# buck_converter.net
KiCad netlist of a schematic drawn in Altium Designer
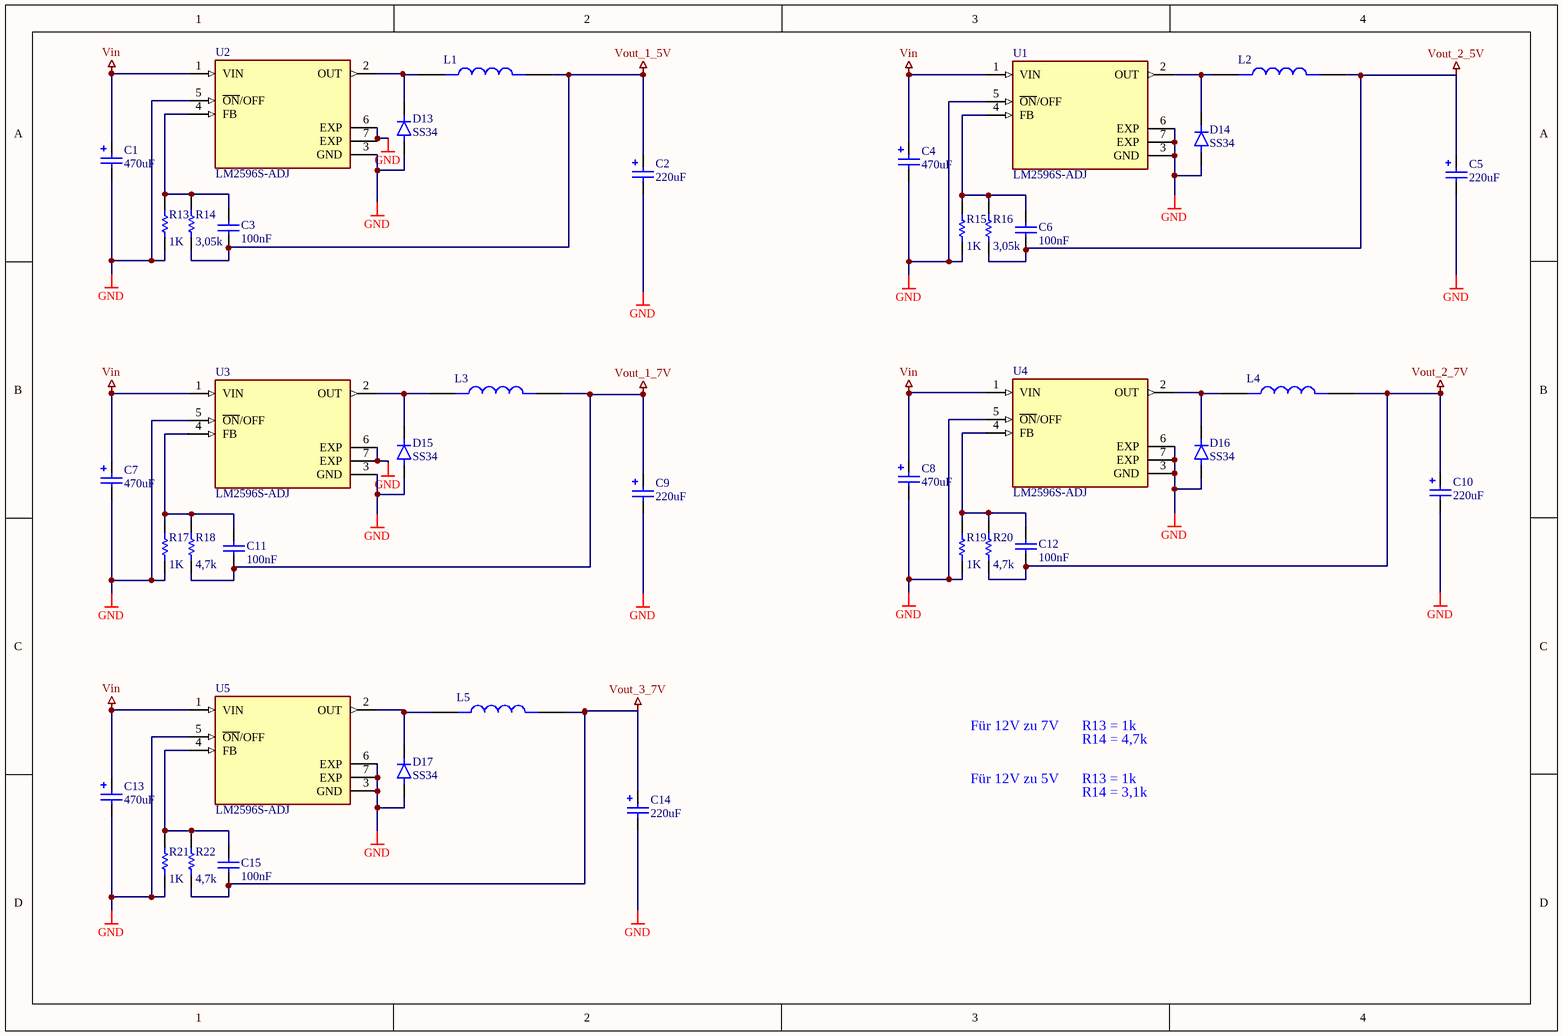
[diagram p0: buck_converter.SchDoc]

(export (version "E")
  (design (tool "Eeschema 10.0.6"))
  (components
    (comp (ref "C1")
      (value "470uF")
      (footprint "CAP_EEEFK1H471AM")
      (description "Elko")
      (fields (field (name "Comment") "Cap"))
      (libsource (lib "HTL-sym-2021_04") (part "ELKO"))
    )
    (comp (ref "C2")
      (value "220uF")
      (footprint "CAPAE1030X1080N_UWT1H221MNL1GS")
      (description "Elko")
      (fields (field (name "Comment") "Cap"))
      (libsource (lib "HTL-sym-2021_04") (part "ELKO"))
    )
    (comp (ref "C3")
      (value "100nF")
      (footprint "RES_ERJB3CFR15V")
      (description "Kondensator")
      (fields (field (name "Comment") "Cap"))
      (libsource (lib "HTL-sym-2021_04") (part "KO"))
    )
    (comp (ref "C4")
      (value "470uF")
      (footprint "CAP_EEEFK1H471AM")
      (description "Elko")
      (fields (field (name "Comment") "Cap"))
      (libsource (lib "HTL-sym-2021_04") (part "ELKO"))
    )
    (comp (ref "C5")
      (value "220uF")
      (footprint "CAPAE1030X1080N_UWT1H221MNL1GS")
      (description "Elko")
      (fields (field (name "Comment") "Cap"))
      (libsource (lib "HTL-sym-2021_04") (part "ELKO"))
    )
    (comp (ref "C6")
      (value "100nF")
      (footprint "RES_ERJB3CFR15V")
      (description "Kondensator")
      (fields (field (name "Comment") "Cap"))
      (libsource (lib "HTL-sym-2021_04") (part "KO"))
    )
    (comp (ref "C7")
      (value "470uF")
      (footprint "CAP_EEEFK1H471AM")
      (description "Elko")
      (fields (field (name "Comment") "Cap"))
      (libsource (lib "HTL-sym-2021_04") (part "ELKO"))
    )
    (comp (ref "C8")
      (value "470uF")
      (footprint "CAP_EEEFK1H471AM")
      (description "Elko")
      (fields (field (name "Comment") "Cap"))
      (libsource (lib "HTL-sym-2021_04") (part "ELKO"))
    )
    (comp (ref "C9")
      (value "220uF")
      (footprint "CAPAE1030X1080N_UWT1H221MNL1GS")
      (description "Elko")
      (fields (field (name "Comment") "Cap"))
      (libsource (lib "HTL-sym-2021_04") (part "ELKO"))
    )
    (comp (ref "C10")
      (value "220uF")
      (footprint "CAPAE1030X1080N_UWT1H221MNL1GS")
      (description "Elko")
      (fields (field (name "Comment") "Cap"))
      (libsource (lib "HTL-sym-2021_04") (part "ELKO"))
    )
    (comp (ref "C11")
      (value "100nF")
      (footprint "RES_ERJB3CFR15V")
      (description "Kondensator")
      (fields (field (name "Comment") "Cap"))
      (libsource (lib "HTL-sym-2021_04") (part "KO"))
    )
    (comp (ref "C12")
      (value "100nF")
      (footprint "RES_ERJB3CFR15V")
      (description "Kondensator")
      (fields (field (name "Comment") "Cap"))
      (libsource (lib "HTL-sym-2021_04") (part "KO"))
    )
    (comp (ref "C13")
      (value "470uF")
      (footprint "CAP_EEEFK1H471AM")
      (description "Elko")
      (fields (field (name "Comment") "Cap"))
      (libsource (lib "HTL-sym-2021_04") (part "ELKO"))
    )
    (comp (ref "C14")
      (value "220uF")
      (footprint "CAPAE1030X1080N_UWT1H221MNL1GS")
      (description "Elko")
      (fields (field (name "Comment") "Cap"))
      (libsource (lib "HTL-sym-2021_04") (part "ELKO"))
    )
    (comp (ref "C15")
      (value "100nF")
      (footprint "RES_ERJB3CFR15V")
      (description "Kondensator")
      (fields (field (name "Comment") "Cap"))
      (libsource (lib "HTL-sym-2021_04") (part "KO"))
    )
    (comp (ref "D13")
      (value "SS34")
      (footprint "DIOMELF3414N")
      (description "Diode Standard 100 V 200mA Surface Mount SOD-80")
      (fields (field (name "MF") "ON Semiconductor") (field (name "MP") "FDLL4148"))
      (libsource (lib "FDLL4148") (part "FDLL4148"))
    )
    (comp (ref "D14")
      (value "SS34")
      (footprint "DIOMELF3414N")
      (description "Diode Standard 100 V 200mA Surface Mount SOD-80")
      (fields (field (name "MF") "ON Semiconductor") (field (name "MP") "FDLL4148"))
      (libsource (lib "FDLL4148") (part "FDLL4148"))
    )
    (comp (ref "D15")
      (value "SS34")
      (footprint "DIOMELF3414N")
      (description "Diode Standard 100 V 200mA Surface Mount SOD-80")
      (fields (field (name "MF") "ON Semiconductor") (field (name "MP") "FDLL4148"))
      (libsource (lib "FDLL4148") (part "FDLL4148"))
    )
    (comp (ref "D16")
      (value "SS34")
      (footprint "DIOMELF3414N")
      (description "Diode Standard 100 V 200mA Surface Mount SOD-80")
      (fields (field (name "MF") "ON Semiconductor") (field (name "MP") "FDLL4148"))
      (libsource (lib "FDLL4148") (part "FDLL4148"))
    )
    (comp (ref "D17")
      (value "SS34")
      (footprint "DIOMELF3414N")
      (description "Diode Standard 100 V 200mA Surface Mount SOD-80")
      (fields (field (name "MF") "ON Semiconductor") (field (name "MP") "FDLL4148"))
      (libsource (lib "FDLL4148") (part "FDLL4148"))
    )
    (comp (ref "L1")
      (value "MLF2012C680KT000")
      (footprint "IND_SRN6045TA-680M")
      (description "68ÂµH Shielded Multilayer Inductor 2mA 2.9Ohm Max 0805 (2012 Metric)")
      (fields (field (name "MF") "{'manufacturer': u'TDK Corporation'}"))
      (libsource (lib "MLF2012C680KT000") (part "MLF2012C680KT000"))
    )
    (comp (ref "L2")
      (value "MLF2012C680KT000")
      (footprint "IND_SRN6045TA-680M")
      (description "68ÂµH Shielded Multilayer Inductor 2mA 2.9Ohm Max 0805 (2012 Metric)")
      (fields (field (name "MF") "{'manufacturer': u'TDK Corporation'}"))
      (libsource (lib "MLF2012C680KT000") (part "MLF2012C680KT000"))
    )
    (comp (ref "L3")
      (value "MLF2012C680KT000")
      (footprint "IND_SRN6045TA-680M")
      (description "68ÂµH Shielded Multilayer Inductor 2mA 2.9Ohm Max 0805 (2012 Metric)")
      (fields (field (name "MF") "{'manufacturer': u'TDK Corporation'}"))
      (libsource (lib "MLF2012C680KT000") (part "MLF2012C680KT000"))
    )
    (comp (ref "L4")
      (value "MLF2012C680KT000")
      (footprint "IND_SRN6045TA-680M")
      (description "68ÂµH Shielded Multilayer Inductor 2mA 2.9Ohm Max 0805 (2012 Metric)")
      (fields (field (name "MF") "{'manufacturer': u'TDK Corporation'}"))
      (libsource (lib "MLF2012C680KT000") (part "MLF2012C680KT000"))
    )
    (comp (ref "L5")
      (value "MLF2012C680KT000")
      (footprint "IND_SRN6045TA-680M")
      (description "68ÂµH Shielded Multilayer Inductor 2mA 2.9Ohm Max 0805 (2012 Metric)")
      (fields (field (name "MF") "{'manufacturer': u'TDK Corporation'}"))
      (libsource (lib "MLF2012C680KT000") (part "MLF2012C680KT000"))
    )
    (comp (ref "R13")
      (value "1K")
      (footprint "RES_ERJB3CFR15V")
      (description "Resistor")
      (fields (field (name "Comment") "Res1") (field (name "PUBLISHER") "Altium Limited"))
      (libsource (lib "Miscellaneous Devices") (part "Res1"))
    )
    (comp (ref "R14")
      (value "3,05k")
      (footprint "RES_ERJB3CFR15V")
      (description "Resistor")
      (fields (field (name "Comment") "Res1") (field (name "PUBLISHER") "Altium Limited"))
      (libsource (lib "Miscellaneous Devices") (part "Res1"))
    )
    (comp (ref "R15")
      (value "1K")
      (footprint "RES_ERJB3CFR15V")
      (description "Resistor")
      (fields (field (name "Comment") "Res1") (field (name "PUBLISHER") "Altium Limited"))
      (libsource (lib "Miscellaneous Devices") (part "Res1"))
    )
    (comp (ref "R16")
      (value "3,05k")
      (footprint "RES_ERJB3CFR15V")
      (description "Resistor")
      (fields (field (name "Comment") "Res1") (field (name "PUBLISHER") "Altium Limited"))
      (libsource (lib "Miscellaneous Devices") (part "Res1"))
    )
    (comp (ref "R17")
      (value "1K")
      (footprint "RES_ERJB3CFR15V")
      (description "Resistor")
      (fields (field (name "Comment") "Res1") (field (name "PUBLISHER") "Altium Limited"))
      (libsource (lib "Miscellaneous Devices") (part "Res1"))
    )
    (comp (ref "R18")
      (value "4,7k")
      (footprint "RES_ERJB3CFR15V")
      (description "Resistor")
      (fields (field (name "Comment") "Res1") (field (name "PUBLISHER") "Altium Limited"))
      (libsource (lib "Miscellaneous Devices") (part "Res1"))
    )
    (comp (ref "R19")
      (value "1K")
      (footprint "RES_ERJB3CFR15V")
      (description "Resistor")
      (fields (field (name "Comment") "Res1") (field (name "PUBLISHER") "Altium Limited"))
      (libsource (lib "Miscellaneous Devices") (part "Res1"))
    )
    (comp (ref "R20")
      (value "4,7k")
      (footprint "RES_ERJB3CFR15V")
      (description "Resistor")
      (fields (field (name "Comment") "Res1") (field (name "PUBLISHER") "Altium Limited"))
      (libsource (lib "Miscellaneous Devices") (part "Res1"))
    )
    (comp (ref "R21")
      (value "1K")
      (footprint "RES_ERJB3CFR15V")
      (description "Resistor")
      (fields (field (name "Comment") "Res1") (field (name "PUBLISHER") "Altium Limited"))
      (libsource (lib "Miscellaneous Devices") (part "Res1"))
    )
    (comp (ref "R22")
      (value "4,7k")
      (footprint "RES_ERJB3CFR15V")
      (description "Resistor")
      (fields (field (name "Comment") "Res1") (field (name "PUBLISHER") "Altium Limited"))
      (libsource (lib "Miscellaneous Devices") (part "Res1"))
    )
    (comp (ref "U1")
      (value "LM2596S-ADJ")
      (footprint "VREG_LM2596SX-5.0_NOPB")
      (description "SIMPLE SWITCHERÂ® 4.5V to 40V, 3A Low Component Count Step-Down Regulator 5-DDPAK/TO-263")
      (fields (field (name "MF") "Texas Instruments") (field (name "MP") "LM2596S-3.3"))
      (libsource (lib "LM2596S-3.3") (part "LM2596S-3.3"))
    )
    (comp (ref "U2")
      (value "LM2596S-ADJ")
      (footprint "VREG_LM2596SX-5.0_NOPB")
      (description "SIMPLE SWITCHERÂ® 4.5V to 40V, 3A Low Component Count Step-Down Regulator 5-DDPAK/TO-263")
      (fields (field (name "MF") "Texas Instruments") (field (name "MP") "LM2596S-3.3"))
      (libsource (lib "LM2596S-3.3") (part "LM2596S-3.3"))
    )
    (comp (ref "U3")
      (value "LM2596S-ADJ")
      (footprint "VREG_LM2596SX-5.0_NOPB")
      (description "SIMPLE SWITCHERÂ® 4.5V to 40V, 3A Low Component Count Step-Down Regulator 5-DDPAK/TO-263")
      (fields (field (name "MF") "Texas Instruments") (field (name "MP") "LM2596S-3.3"))
      (libsource (lib "LM2596S-3.3") (part "LM2596S-3.3"))
    )
    (comp (ref "U4")
      (value "LM2596S-ADJ")
      (footprint "VREG_LM2596SX-5.0_NOPB")
      (description "SIMPLE SWITCHERÂ® 4.5V to 40V, 3A Low Component Count Step-Down Regulator 5-DDPAK/TO-263")
      (fields (field (name "MF") "Texas Instruments") (field (name "MP") "LM2596S-3.3"))
      (libsource (lib "LM2596S-3.3") (part "LM2596S-3.3"))
    )
    (comp (ref "U5")
      (value "LM2596S-ADJ")
      (footprint "VREG_LM2596SX-5.0_NOPB")
      (description "SIMPLE SWITCHERÂ® 4.5V to 40V, 3A Low Component Count Step-Down Regulator 5-DDPAK/TO-263")
      (fields (field (name "MF") "Texas Instruments") (field (name "MP") "LM2596S-3.3"))
      (libsource (lib "LM2596S-3.3") (part "LM2596S-3.3"))
    )
  )
  (nets
    (net (code "1") (name "GND") (class "Default")
      (node (ref "C1") (pin "2") (pinfunction "2_2") (pintype "passive"))
      (node (ref "C10") (pin "2") (pinfunction "2_2") (pintype "passive"))
      (node (ref "C13") (pin "2") (pinfunction "2_2") (pintype "passive"))
      (node (ref "C14") (pin "2") (pinfunction "2_2") (pintype "passive"))
      (node (ref "C2") (pin "2") (pinfunction "2_2") (pintype "passive"))
      (node (ref "C4") (pin "2") (pinfunction "2_2") (pintype "passive"))
      (node (ref "C5") (pin "2") (pinfunction "2_2") (pintype "passive"))
      (node (ref "C7") (pin "2") (pinfunction "2_2") (pintype "passive"))
      (node (ref "C8") (pin "2") (pinfunction "2_2") (pintype "passive"))
      (node (ref "C9") (pin "2") (pinfunction "2_2") (pintype "passive"))
      (node (ref "D13") (pin "A") (pinfunction "A_A") (pintype "passive"))
      (node (ref "D14") (pin "A") (pinfunction "A_A") (pintype "passive"))
      (node (ref "D15") (pin "A") (pinfunction "A_A") (pintype "passive"))
      (node (ref "D16") (pin "A") (pinfunction "A_A") (pintype "passive"))
      (node (ref "D17") (pin "A") (pinfunction "A_A") (pintype "passive"))
      (node (ref "R13") (pin "1") (pinfunction "1_1") (pintype "passive"))
      (node (ref "R15") (pin "1") (pinfunction "1_1") (pintype "passive"))
      (node (ref "R17") (pin "1") (pinfunction "1_1") (pintype "passive"))
      (node (ref "R19") (pin "1") (pinfunction "1_1") (pintype "passive"))
      (node (ref "R21") (pin "1") (pinfunction "1_1") (pintype "passive"))
      (node (ref "U1") (pin "3") (pinfunction "GND_3") (pintype "power_in"))
      (node (ref "U1") (pin "5") (pinfunction "~{ON}/OFF_5") (pintype "input"))
      (node (ref "U1") (pin "6") (pinfunction "EXP_6") (pintype "power_in"))
      (node (ref "U1") (pin "7") (pinfunction "EXP_7") (pintype "power_in"))
      (node (ref "U2") (pin "3") (pinfunction "GND_3") (pintype "power_in"))
      (node (ref "U2") (pin "5") (pinfunction "~{ON}/OFF_5") (pintype "input"))
      (node (ref "U2") (pin "6") (pinfunction "EXP_6") (pintype "power_in"))
      (node (ref "U2") (pin "7") (pinfunction "EXP_7") (pintype "power_in"))
      (node (ref "U3") (pin "3") (pinfunction "GND_3") (pintype "power_in"))
      (node (ref "U3") (pin "5") (pinfunction "~{ON}/OFF_5") (pintype "input"))
      (node (ref "U3") (pin "6") (pinfunction "EXP_6") (pintype "power_in"))
      (node (ref "U3") (pin "7") (pinfunction "EXP_7") (pintype "power_in"))
      (node (ref "U4") (pin "3") (pinfunction "GND_3") (pintype "power_in"))
      (node (ref "U4") (pin "5") (pinfunction "~{ON}/OFF_5") (pintype "input"))
      (node (ref "U4") (pin "6") (pinfunction "EXP_6") (pintype "power_in"))
      (node (ref "U4") (pin "7") (pinfunction "EXP_7") (pintype "power_in"))
      (node (ref "U5") (pin "3") (pinfunction "GND_3") (pintype "power_in"))
      (node (ref "U5") (pin "5") (pinfunction "~{ON}/OFF_5") (pintype "input"))
      (node (ref "U5") (pin "6") (pinfunction "EXP_6") (pintype "power_in"))
      (node (ref "U5") (pin "7") (pinfunction "EXP_7") (pintype "power_in"))
    )
    (net (code "2") (name "Net-(U1-FB)") (class "Default")
      (node (ref "C6") (pin "1") (pintype "passive"))
      (node (ref "R15") (pin "2") (pinfunction "2_2") (pintype "passive"))
      (node (ref "R16") (pin "2") (pinfunction "2_2") (pintype "passive"))
      (node (ref "U1") (pin "4") (pinfunction "FB_4") (pintype "input"))
    )
    (net (code "3") (name "Net-(U1-OUT)") (class "Default")
      (node (ref "D14") (pin "C") (pinfunction "C_C") (pintype "passive"))
      (node (ref "L2") (pin "1") (pinfunction "1_1") (pintype "passive"))
      (node (ref "U1") (pin "2") (pinfunction "OUT_2") (pintype "output"))
    )
    (net (code "4") (name "Net-(U2-FB)") (class "Default")
      (node (ref "C3") (pin "1") (pintype "passive"))
      (node (ref "R13") (pin "2") (pinfunction "2_2") (pintype "passive"))
      (node (ref "R14") (pin "2") (pinfunction "2_2") (pintype "passive"))
      (node (ref "U2") (pin "4") (pinfunction "FB_4") (pintype "input"))
    )
    (net (code "5") (name "Net-(U2-OUT)") (class "Default")
      (node (ref "D13") (pin "C") (pinfunction "C_C") (pintype "passive"))
      (node (ref "L1") (pin "1") (pinfunction "1_1") (pintype "passive"))
      (node (ref "U2") (pin "2") (pinfunction "OUT_2") (pintype "output"))
    )
    (net (code "6") (name "Net-(U3-FB)") (class "Default")
      (node (ref "C11") (pin "1") (pintype "passive"))
      (node (ref "R17") (pin "2") (pinfunction "2_2") (pintype "passive"))
      (node (ref "R18") (pin "2") (pinfunction "2_2") (pintype "passive"))
      (node (ref "U3") (pin "4") (pinfunction "FB_4") (pintype "input"))
    )
    (net (code "7") (name "Net-(U3-OUT)") (class "Default")
      (node (ref "D15") (pin "C") (pinfunction "C_C") (pintype "passive"))
      (node (ref "L3") (pin "1") (pinfunction "1_1") (pintype "passive"))
      (node (ref "U3") (pin "2") (pinfunction "OUT_2") (pintype "output"))
    )
    (net (code "8") (name "Net-(U4-FB)") (class "Default")
      (node (ref "C12") (pin "1") (pintype "passive"))
      (node (ref "R19") (pin "2") (pinfunction "2_2") (pintype "passive"))
      (node (ref "R20") (pin "2") (pinfunction "2_2") (pintype "passive"))
      (node (ref "U4") (pin "4") (pinfunction "FB_4") (pintype "input"))
    )
    (net (code "9") (name "Net-(U4-OUT)") (class "Default")
      (node (ref "D16") (pin "C") (pinfunction "C_C") (pintype "passive"))
      (node (ref "L4") (pin "1") (pinfunction "1_1") (pintype "passive"))
      (node (ref "U4") (pin "2") (pinfunction "OUT_2") (pintype "output"))
    )
    (net (code "10") (name "Net-(U5-FB)") (class "Default")
      (node (ref "C15") (pin "1") (pintype "passive"))
      (node (ref "R21") (pin "2") (pinfunction "2_2") (pintype "passive"))
      (node (ref "R22") (pin "2") (pinfunction "2_2") (pintype "passive"))
      (node (ref "U5") (pin "4") (pinfunction "FB_4") (pintype "input"))
    )
    (net (code "11") (name "Net-(U5-OUT)") (class "Default")
      (node (ref "D17") (pin "C") (pinfunction "C_C") (pintype "passive"))
      (node (ref "L5") (pin "1") (pinfunction "1_1") (pintype "passive"))
      (node (ref "U5") (pin "2") (pinfunction "OUT_2") (pintype "output"))
    )
    (net (code "12") (name "Vin") (class "Default")
      (node (ref "C1") (pin "1") (pinfunction "1_1") (pintype "passive"))
      (node (ref "C13") (pin "1") (pinfunction "1_1") (pintype "passive"))
      (node (ref "C4") (pin "1") (pinfunction "1_1") (pintype "passive"))
      (node (ref "C7") (pin "1") (pinfunction "1_1") (pintype "passive"))
      (node (ref "C8") (pin "1") (pinfunction "1_1") (pintype "passive"))
      (node (ref "U1") (pin "1") (pinfunction "VIN_1") (pintype "input"))
      (node (ref "U2") (pin "1") (pinfunction "VIN_1") (pintype "input"))
      (node (ref "U3") (pin "1") (pinfunction "VIN_1") (pintype "input"))
      (node (ref "U4") (pin "1") (pinfunction "VIN_1") (pintype "input"))
      (node (ref "U5") (pin "1") (pinfunction "VIN_1") (pintype "input"))
    )
    (net (code "13") (name "Vout_1_5V") (class "Default")
      (node (ref "C2") (pin "1") (pinfunction "1_1") (pintype "passive"))
      (node (ref "C3") (pin "2") (pintype "passive"))
      (node (ref "L1") (pin "2") (pinfunction "2_2") (pintype "passive"))
      (node (ref "R14") (pin "1") (pinfunction "1_1") (pintype "passive"))
    )
    (net (code "14") (name "Vout_1_7V") (class "Default")
      (node (ref "C11") (pin "2") (pintype "passive"))
      (node (ref "C9") (pin "1") (pinfunction "1_1") (pintype "passive"))
      (node (ref "L3") (pin "2") (pinfunction "2_2") (pintype "passive"))
      (node (ref "R18") (pin "1") (pinfunction "1_1") (pintype "passive"))
    )
    (net (code "15") (name "Vout_2_5V") (class "Default")
      (node (ref "C5") (pin "1") (pinfunction "1_1") (pintype "passive"))
      (node (ref "C6") (pin "2") (pintype "passive"))
      (node (ref "L2") (pin "2") (pinfunction "2_2") (pintype "passive"))
      (node (ref "R16") (pin "1") (pinfunction "1_1") (pintype "passive"))
    )
    (net (code "16") (name "Vout_2_7V") (class "Default")
      (node (ref "C10") (pin "1") (pinfunction "1_1") (pintype "passive"))
      (node (ref "C12") (pin "2") (pintype "passive"))
      (node (ref "L4") (pin "2") (pinfunction "2_2") (pintype "passive"))
      (node (ref "R20") (pin "1") (pinfunction "1_1") (pintype "passive"))
    )
    (net (code "17") (name "Vout_3_7V") (class "Default")
      (node (ref "C14") (pin "1") (pinfunction "1_1") (pintype "passive"))
      (node (ref "C15") (pin "2") (pintype "passive"))
      (node (ref "L5") (pin "2") (pinfunction "2_2") (pintype "passive"))
      (node (ref "R22") (pin "1") (pinfunction "1_1") (pintype "passive"))
    )
  )
)
